# Wise-1570-v1_0.net
KiCad netlist of a schematic drawn in EAGLE
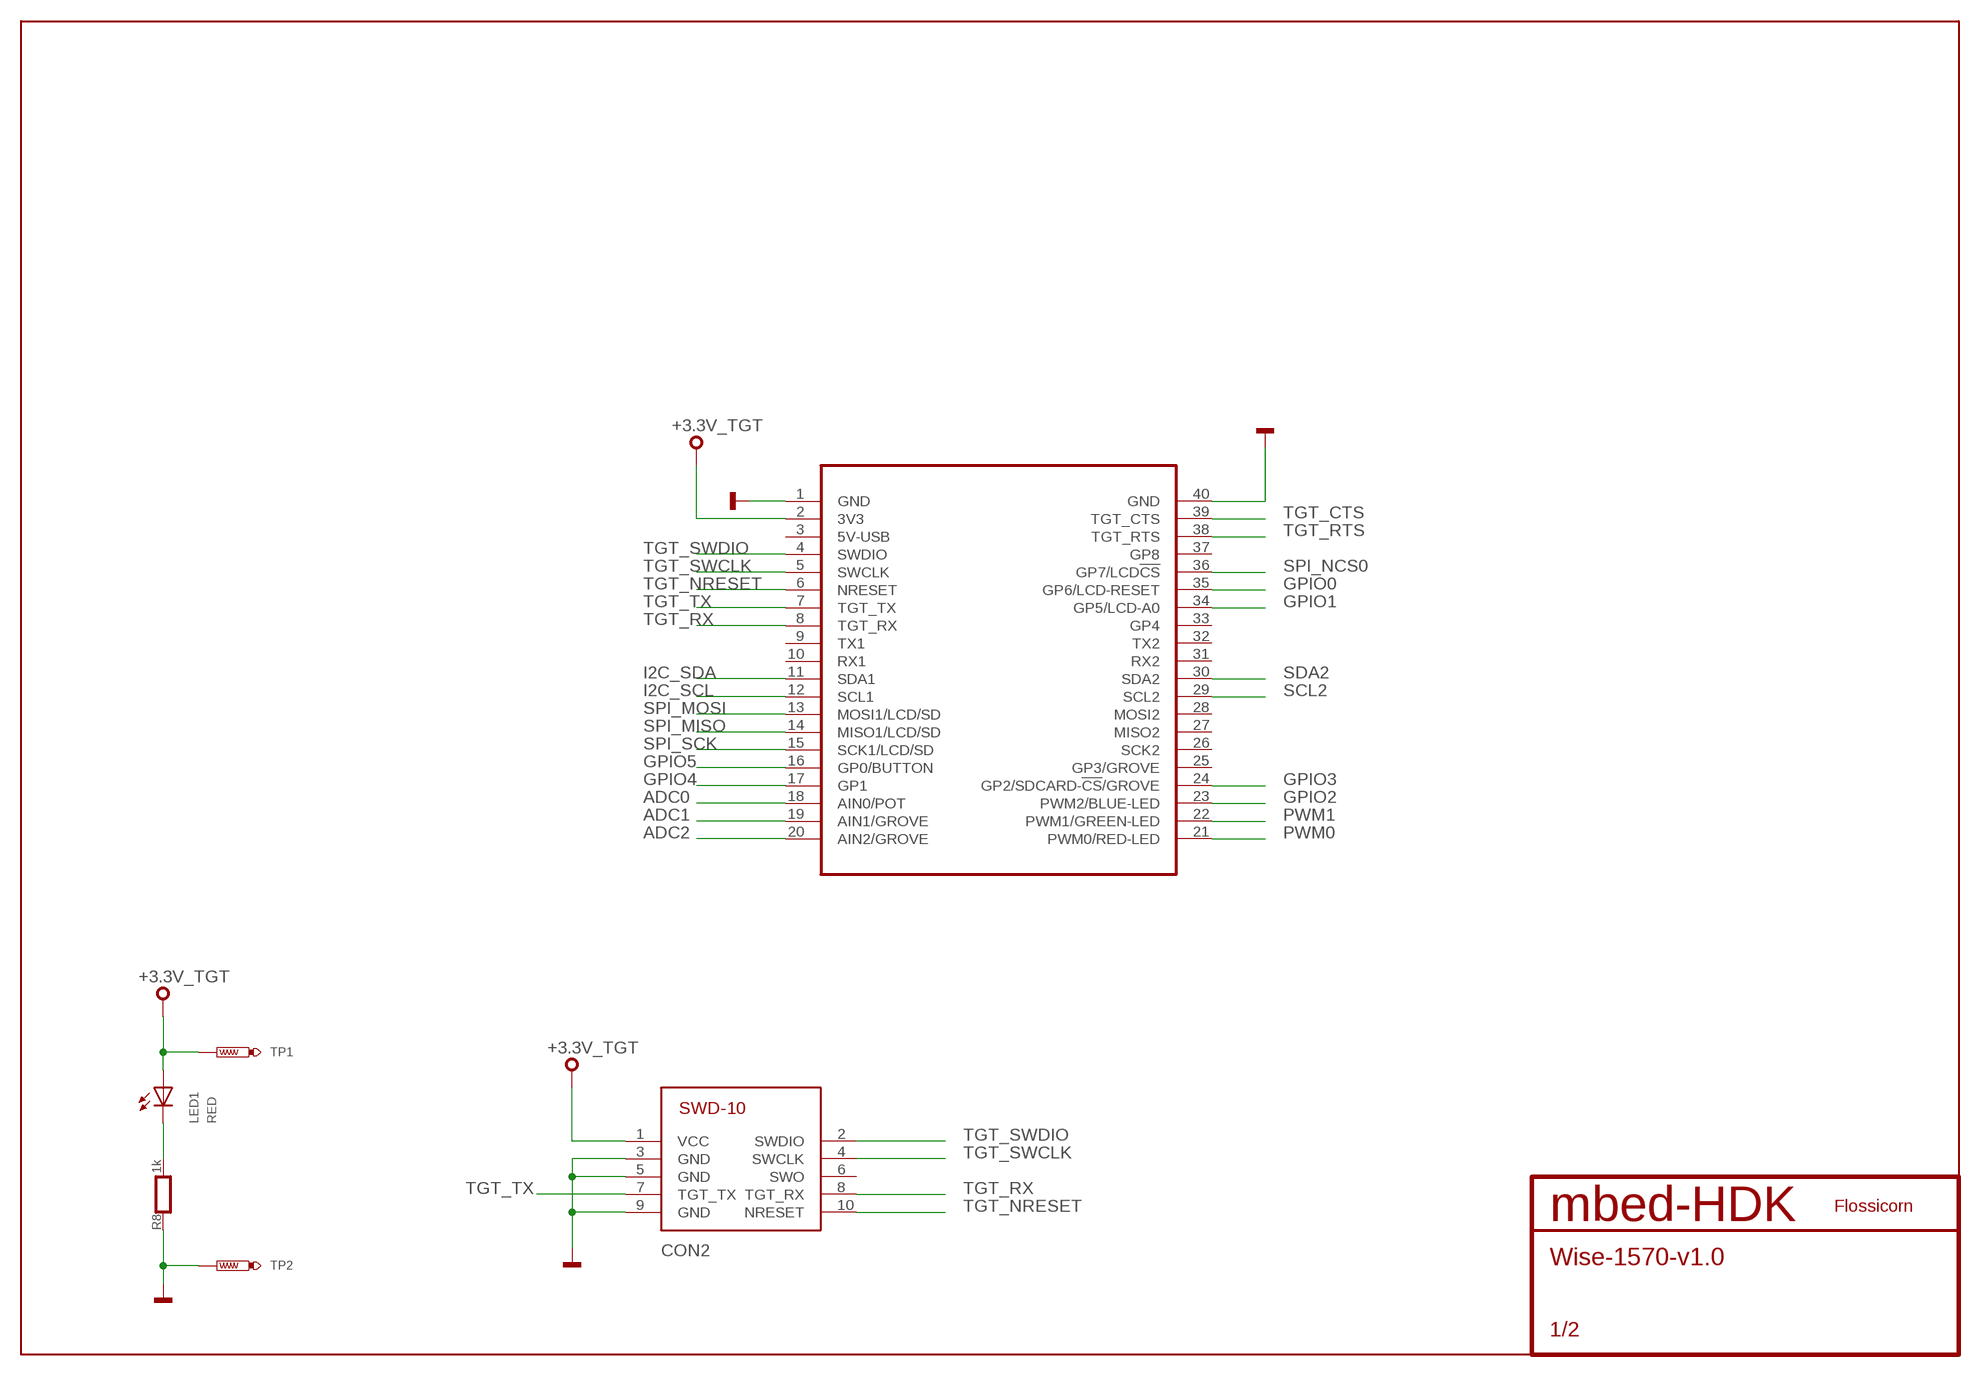
[diagram p0: schematic, sheet 1]
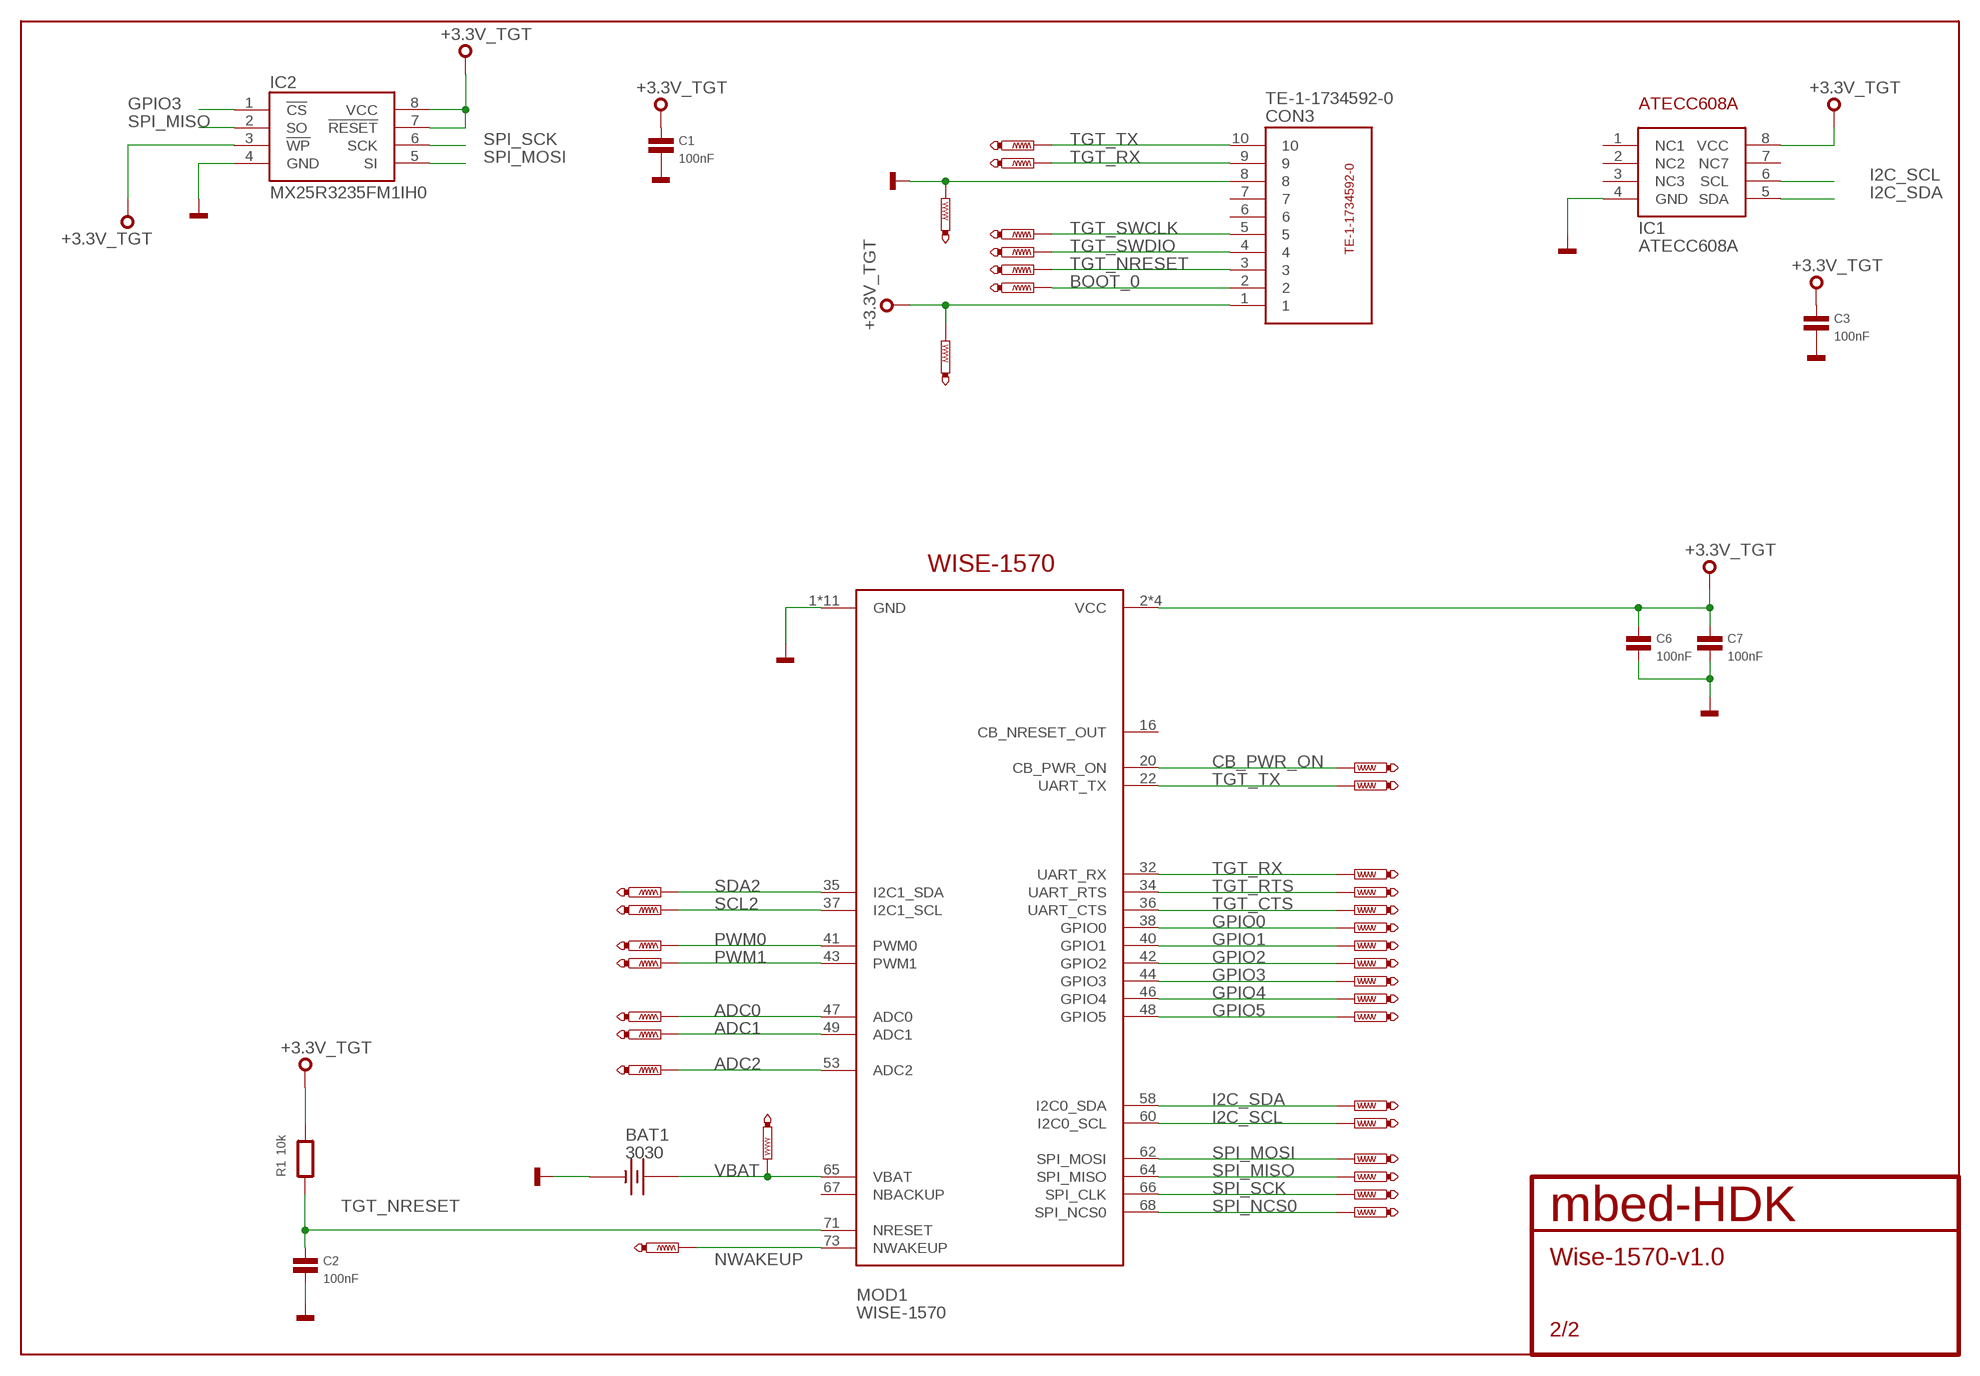
[diagram p1: schematic, sheet 2]

(export (version "E")
  (design (tool "Eeschema 10.0.6"))
  (components
    (comp (ref "CON2")
      (value "SWD-10/TC2050_SMD")
      (footprint "eagle-import:FTSH-105-02")
      (libsource (lib "eagle-import") (part "SWD-10/TC2050_SMD"))
    )
    (comp (ref "LED1")
      (value "RED")
      (footprint "eagle-import:CHIPLED_0603")
      (fields (field (name "MF") "Wurth Electronics Inc"))
      (libsource (lib "eagle-import") (part "SMD_LED0603"))
    )
    (comp (ref "MOD2")
      (value "MODULE_DAUGHTER")
      (footprint "eagle-import:MODULE_DAUGHTER")
      (libsource (lib "eagle-import") (part "MODULE_DAUGHTER"))
    )
    (comp (ref "R8")
      (value "1k")
      (footprint "eagle-import:0603")
      (libsource (lib "eagle-import") (part "RESISTOR0603"))
    )
    (comp (ref "SS1")
      (value "FLOSSICORN0.25")
      (footprint "eagle-import:FLOSSICORN-0.25")
      (libsource (lib "eagle-import") (part "FLOSSICORN0.25"))
    )
    (comp (ref "TP1")
      (value "TEST-POINT-50R-PTH")
      (footprint "eagle-import:TP50-PTH")
      (libsource (lib "eagle-import") (part "TEST-POINT-50R-PTH"))
    )
    (comp (ref "TP2")
      (value "TEST-POINT-50R-PTH")
      (footprint "eagle-import:TP50-PTH")
      (libsource (lib "eagle-import") (part "TEST-POINT-50R-PTH"))
    )
    (comp (ref "BAT1")
      (value "3030")
      (footprint "eagle-import:3030")
      (fields (field (name "MF") "Keystone"))
      (libsource (lib "eagle-import") (part "3030"))
    )
    (comp (ref "C1")
      (value "100nF")
      (footprint "eagle-import:0603")
      (libsource (lib "eagle-import") (part "CAPACITOR0603"))
    )
    (comp (ref "C2")
      (value "100nF")
      (footprint "eagle-import:0603")
      (libsource (lib "eagle-import") (part "CAPACITOR0603"))
    )
    (comp (ref "C3")
      (value "100nF")
      (footprint "eagle-import:0603")
      (libsource (lib "eagle-import") (part "CAPACITOR0603"))
    )
    (comp (ref "C6")
      (value "100nF")
      (footprint "eagle-import:0603")
      (libsource (lib "eagle-import") (part "CAPACITOR0603"))
    )
    (comp (ref "C7")
      (value "100nF")
      (footprint "eagle-import:0603")
      (libsource (lib "eagle-import") (part "CAPACITOR0603"))
    )
    (comp (ref "CON3")
      (value "TE-1-1734592-0")
      (footprint "eagle-import:TE-1-1734592-0")
      (libsource (lib "eagle-import") (part "TE-1-1734592-0"))
    )
    (comp (ref "IC1")
      (value "ATECC608A")
      (footprint "eagle-import:SO8")
      (libsource (lib "eagle-import") (part "ATECC608A"))
    )
    (comp (ref "IC2")
      (value "MX25R3235FM1IH0")
      (footprint "eagle-import:SO8")
      (fields (field (name "MF") "Macronix"))
      (libsource (lib "eagle-import") (part "MX25R3235FM1IH0"))
    )
    (comp (ref "MOD1")
      (value "WISE-1570")
      (footprint "eagle-import:MDT420E02001")
      (libsource (lib "eagle-import") (part "WISE-1570"))
    )
    (comp (ref "R1")
      (value "10k")
      (footprint "eagle-import:0603")
      (libsource (lib "eagle-import") (part "RESISTOR0603"))
    )
    (comp (ref "TP3")
      (value "PTR1TP08R")
      (footprint "eagle-import:TP08R")
      (libsource (lib "eagle-import") (part "PTR1TP08R"))
    )
    (comp (ref "TP4")
      (value "PTR1TP08R")
      (footprint "eagle-import:TP08R")
      (libsource (lib "eagle-import") (part "PTR1TP08R"))
    )
    (comp (ref "TP5")
      (value "PTR1TP08R")
      (footprint "eagle-import:TP08R")
      (libsource (lib "eagle-import") (part "PTR1TP08R"))
    )
    (comp (ref "TP6")
      (value "PTR1TP08R")
      (footprint "eagle-import:TP08R")
      (libsource (lib "eagle-import") (part "PTR1TP08R"))
    )
    (comp (ref "TP7")
      (value "PTR1TP08R")
      (footprint "eagle-import:TP08R")
      (libsource (lib "eagle-import") (part "PTR1TP08R"))
    )
    (comp (ref "TP8")
      (value "PTR1TP08R")
      (footprint "eagle-import:TP08R")
      (libsource (lib "eagle-import") (part "PTR1TP08R"))
    )
    (comp (ref "TP9")
      (value "PTR1TP07R")
      (footprint "eagle-import:TP07R")
      (libsource (lib "eagle-import") (part "PTR1TP07R"))
    )
    (comp (ref "TP10")
      (value "PTR1TP07R")
      (footprint "eagle-import:TP07R")
      (libsource (lib "eagle-import") (part "PTR1TP07R"))
    )
    (comp (ref "TP11")
      (value "PTR1TP07R")
      (footprint "eagle-import:TP07R")
      (libsource (lib "eagle-import") (part "PTR1TP07R"))
    )
    (comp (ref "TP12")
      (value "PTR1TP08R")
      (footprint "eagle-import:TP08R")
      (libsource (lib "eagle-import") (part "PTR1TP08R"))
    )
    (comp (ref "TP13")
      (value "PTR1TP08R")
      (footprint "eagle-import:TP08R")
      (libsource (lib "eagle-import") (part "PTR1TP08R"))
    )
    (comp (ref "TP14")
      (value "PTR1TP07R")
      (footprint "eagle-import:TP07R")
      (libsource (lib "eagle-import") (part "PTR1TP07R"))
    )
    (comp (ref "TP15")
      (value "PTR1TP07R")
      (footprint "eagle-import:TP07R")
      (libsource (lib "eagle-import") (part "PTR1TP07R"))
    )
    (comp (ref "TP16")
      (value "PTR1TP07R")
      (footprint "eagle-import:TP07R")
      (libsource (lib "eagle-import") (part "PTR1TP07R"))
    )
    (comp (ref "TP17")
      (value "PTR1TP07R")
      (footprint "eagle-import:TP07R")
      (libsource (lib "eagle-import") (part "PTR1TP07R"))
    )
    (comp (ref "TP18")
      (value "PTR1TP07R")
      (footprint "eagle-import:TP07R")
      (libsource (lib "eagle-import") (part "PTR1TP07R"))
    )
    (comp (ref "TP19")
      (value "PTR1TP07R")
      (footprint "eagle-import:TP07R")
      (libsource (lib "eagle-import") (part "PTR1TP07R"))
    )
    (comp (ref "TP20")
      (value "PTR1TP07R")
      (footprint "eagle-import:TP07R")
      (libsource (lib "eagle-import") (part "PTR1TP07R"))
    )
    (comp (ref "TP21")
      (value "PTR1TP07R")
      (footprint "eagle-import:TP07R")
      (libsource (lib "eagle-import") (part "PTR1TP07R"))
    )
    (comp (ref "TP22")
      (value "PTR1TP07R")
      (footprint "eagle-import:TP07R")
      (libsource (lib "eagle-import") (part "PTR1TP07R"))
    )
    (comp (ref "TP23")
      (value "PTR1TP07R")
      (footprint "eagle-import:TP07R")
      (libsource (lib "eagle-import") (part "PTR1TP07R"))
    )
    (comp (ref "TP24")
      (value "PTR1TP07R")
      (footprint "eagle-import:TP07R")
      (libsource (lib "eagle-import") (part "PTR1TP07R"))
    )
    (comp (ref "TP25")
      (value "PTR1TP07R")
      (footprint "eagle-import:TP07R")
      (libsource (lib "eagle-import") (part "PTR1TP07R"))
    )
    (comp (ref "TP26")
      (value "PTR1TP07R")
      (footprint "eagle-import:TP07R")
      (libsource (lib "eagle-import") (part "PTR1TP07R"))
    )
    (comp (ref "TP27")
      (value "PTR1TP07R")
      (footprint "eagle-import:TP07R")
      (libsource (lib "eagle-import") (part "PTR1TP07R"))
    )
    (comp (ref "TP28")
      (value "PTR1TP07R")
      (footprint "eagle-import:TP07R")
      (libsource (lib "eagle-import") (part "PTR1TP07R"))
    )
    (comp (ref "TP29")
      (value "PTR1TP07R")
      (footprint "eagle-import:TP07R")
      (libsource (lib "eagle-import") (part "PTR1TP07R"))
    )
    (comp (ref "TP30")
      (value "PTR1TP07R")
      (footprint "eagle-import:TP07R")
      (libsource (lib "eagle-import") (part "PTR1TP07R"))
    )
    (comp (ref "TP31")
      (value "PTR1TP07R")
      (footprint "eagle-import:TP07R")
      (libsource (lib "eagle-import") (part "PTR1TP07R"))
    )
    (comp (ref "TP32")
      (value "PTR1TP07R")
      (footprint "eagle-import:TP07R")
      (libsource (lib "eagle-import") (part "PTR1TP07R"))
    )
    (comp (ref "TP33")
      (value "PTR1TP07R")
      (footprint "eagle-import:TP07R")
      (libsource (lib "eagle-import") (part "PTR1TP07R"))
    )
    (comp (ref "TP34")
      (value "PTR1TP07R")
      (footprint "eagle-import:TP07R")
      (libsource (lib "eagle-import") (part "PTR1TP07R"))
    )
    (comp (ref "TP35")
      (value "PTR1TP07R")
      (footprint "eagle-import:TP07R")
      (libsource (lib "eagle-import") (part "PTR1TP07R"))
    )
    (comp (ref "TP36")
      (value "PTR1TP07R")
      (footprint "eagle-import:TP07R")
      (libsource (lib "eagle-import") (part "PTR1TP07R"))
    )
  )
  (nets
    (net (code "1") (name "+3.3V_TGT") (class "Default")
      (node (ref "C1") (pin "1") (pinfunction "P$1_1") (pintype "passive"))
      (node (ref "C3") (pin "1") (pinfunction "P$1_1") (pintype "passive"))
      (node (ref "C6") (pin "1") (pinfunction "P$1_1") (pintype "passive"))
      (node (ref "C7") (pin "1") (pinfunction "P$1_1") (pintype "passive"))
      (node (ref "CON2") (pin "1") (pinfunction "VCC_1") (pintype "bidirectional"))
      (node (ref "CON3") (pin "1") (pinfunction "1_1") (pintype "bidirectional"))
      (node (ref "IC1") (pin "8") (pinfunction "VCC_8") (pintype "bidirectional"))
      (node (ref "IC2") (pin "3") (pinfunction "~{WP}_3") (pintype "bidirectional"))
      (node (ref "IC2") (pin "7") (pinfunction "~{RESET}_7") (pintype "bidirectional"))
      (node (ref "IC2") (pin "8") (pinfunction "VCC_8") (pintype "bidirectional"))
      (node (ref "LED1") (pin "A") (pinfunction "A_A") (pintype "passive"))
      (node (ref "MOD1") (pin "2") (pinfunction "VCC_2") (pintype "bidirectional"))
      (node (ref "MOD1") (pin "4") (pinfunction "VCC_4") (pintype "bidirectional"))
      (node (ref "MOD1") (pin "72") (pinfunction "VCC_72") (pintype "bidirectional"))
      (node (ref "MOD1") (pin "74") (pinfunction "VCC_74") (pintype "bidirectional"))
      (node (ref "MOD2") (pin "2") (pinfunction "3V3_2") (pintype "bidirectional"))
      (node (ref "R1") (pin "2") (pinfunction "P$2_2") (pintype "passive"))
      (node (ref "TP1") (pin "TP") (pinfunction "TP_TP") (pintype "input"))
      (node (ref "TP12") (pin "TP") (pinfunction "TP_TP") (pintype "input"))
    )
    (net (code "2") (name "ADC0") (class "Default")
      (node (ref "MOD1") (pin "47") (pinfunction "ADC0_47") (pintype "bidirectional"))
      (node (ref "MOD2") (pin "18") (pinfunction "AIN0/POT_18") (pintype "bidirectional"))
      (node (ref "TP29") (pin "TP") (pinfunction "TP_TP") (pintype "input"))
    )
    (net (code "3") (name "ADC1") (class "Default")
      (node (ref "MOD1") (pin "49") (pinfunction "ADC1_49") (pintype "bidirectional"))
      (node (ref "MOD2") (pin "19") (pinfunction "AIN1/GROVE_19") (pintype "bidirectional"))
      (node (ref "TP30") (pin "TP") (pinfunction "TP_TP") (pintype "input"))
    )
    (net (code "4") (name "ADC2") (class "Default")
      (node (ref "MOD1") (pin "53") (pinfunction "ADC2_53") (pintype "bidirectional"))
      (node (ref "MOD2") (pin "20") (pinfunction "AIN2/GROVE_20") (pintype "bidirectional"))
      (node (ref "TP31") (pin "TP") (pinfunction "TP_TP") (pintype "input"))
    )
    (net (code "5") (name "BOOT_0") (class "Default")
      (node (ref "CON3") (pin "2") (pinfunction "2_2") (pintype "bidirectional"))
      (node (ref "TP8") (pin "TP") (pinfunction "TP_TP") (pintype "input"))
    )
    (net (code "6") (name "CB_PWR_ON") (class "Default")
      (node (ref "MOD1") (pin "20") (pinfunction "CB_PWR_ON_20") (pintype "bidirectional"))
      (node (ref "TP14") (pin "TP") (pinfunction "TP_TP") (pintype "input"))
    )
    (net (code "7") (name "GND") (class "Default")
      (node (ref "BAT1") (pin "-") (pinfunction "-_-") (pintype "bidirectional"))
      (node (ref "C1") (pin "2") (pinfunction "P$2_2") (pintype "passive"))
      (node (ref "C2") (pin "2") (pinfunction "P$2_2") (pintype "passive"))
      (node (ref "C3") (pin "2") (pinfunction "P$2_2") (pintype "passive"))
      (node (ref "C6") (pin "2") (pinfunction "P$2_2") (pintype "passive"))
      (node (ref "C7") (pin "2") (pinfunction "P$2_2") (pintype "passive"))
      (node (ref "CON2") (pin "3") (pinfunction "GND_3") (pintype "bidirectional"))
      (node (ref "CON2") (pin "5") (pinfunction "GND_5") (pintype "bidirectional"))
      (node (ref "CON2") (pin "9") (pinfunction "GND_9") (pintype "bidirectional"))
      (node (ref "CON3") (pin "8") (pinfunction "8_8") (pintype "bidirectional"))
      (node (ref "IC1") (pin "4") (pinfunction "GND_4") (pintype "bidirectional"))
      (node (ref "IC2") (pin "4") (pinfunction "GND_4") (pintype "bidirectional"))
      (node (ref "MOD1") (pin "1") (pinfunction "GND_1") (pintype "bidirectional"))
      (node (ref "MOD1") (pin "18") (pinfunction "GND_18") (pintype "bidirectional"))
      (node (ref "MOD1") (pin "33") (pinfunction "GND_33") (pintype "bidirectional"))
      (node (ref "MOD1") (pin "39") (pinfunction "GND_39") (pintype "bidirectional"))
      (node (ref "MOD1") (pin "45") (pinfunction "GND_45") (pintype "bidirectional"))
      (node (ref "MOD1") (pin "51") (pinfunction "GND_51") (pintype "bidirectional"))
      (node (ref "MOD1") (pin "57") (pinfunction "GND_57") (pintype "bidirectional"))
      (node (ref "MOD1") (pin "63") (pinfunction "GND_63") (pintype "bidirectional"))
      (node (ref "MOD1") (pin "69") (pinfunction "GND_69") (pintype "bidirectional"))
      (node (ref "MOD1") (pin "7") (pinfunction "GND_7") (pintype "bidirectional"))
      (node (ref "MOD1") (pin "75") (pinfunction "GND_75") (pintype "bidirectional"))
      (node (ref "MOD2") (pin "1") (pinfunction "GND_1") (pintype "bidirectional"))
      (node (ref "MOD2") (pin "40") (pinfunction "GND_40") (pintype "bidirectional"))
      (node (ref "R8") (pin "1") (pinfunction "P$1_1") (pintype "passive"))
      (node (ref "TP13") (pin "TP") (pinfunction "TP_TP") (pintype "input"))
      (node (ref "TP2") (pin "TP") (pinfunction "TP_TP") (pintype "input"))
    )
    (net (code "8") (name "GPIO0") (class "Default")
      (node (ref "MOD1") (pin "38") (pinfunction "GPIO0_38") (pintype "bidirectional"))
      (node (ref "MOD2") (pin "35") (pinfunction "GP6/LCD-RESET_35") (pintype "bidirectional"))
      (node (ref "TP27") (pin "TP") (pinfunction "TP_TP") (pintype "input"))
    )
    (net (code "9") (name "GPIO1") (class "Default")
      (node (ref "MOD1") (pin "40") (pinfunction "GPIO1_40") (pintype "bidirectional"))
      (node (ref "MOD2") (pin "34") (pinfunction "GP5/LCD-A0_34") (pintype "bidirectional"))
      (node (ref "TP26") (pin "TP") (pinfunction "TP_TP") (pintype "input"))
    )
    (net (code "10") (name "GPIO2") (class "Default")
      (node (ref "MOD1") (pin "42") (pinfunction "GPIO2_42") (pintype "bidirectional"))
      (node (ref "MOD2") (pin "23") (pinfunction "PWM2/BLUE-LED_23") (pintype "bidirectional"))
      (node (ref "TP32") (pin "TP") (pinfunction "TP_TP") (pintype "input"))
    )
    (net (code "11") (name "GPIO3") (class "Default")
      (node (ref "IC2") (pin "1") (pinfunction "~{CS}_1") (pintype "bidirectional"))
      (node (ref "MOD1") (pin "44") (pinfunction "GPIO3_44") (pintype "bidirectional"))
      (node (ref "MOD2") (pin "24") (pinfunction "GP2/SDCARD-~{CS}/GROVE_24") (pintype "bidirectional"))
      (node (ref "TP25") (pin "TP") (pinfunction "TP_TP") (pintype "input"))
    )
    (net (code "12") (name "GPIO4") (class "Default")
      (node (ref "MOD1") (pin "46") (pinfunction "GPIO4_46") (pintype "bidirectional"))
      (node (ref "MOD2") (pin "17") (pinfunction "GP1_17") (pintype "bidirectional"))
      (node (ref "TP24") (pin "TP") (pinfunction "TP_TP") (pintype "input"))
    )
    (net (code "13") (name "GPIO5") (class "Default")
      (node (ref "MOD1") (pin "48") (pinfunction "GPIO5_48") (pintype "bidirectional"))
      (node (ref "MOD2") (pin "16") (pinfunction "GP0/BUTTON_16") (pintype "bidirectional"))
      (node (ref "TP23") (pin "TP") (pinfunction "TP_TP") (pintype "input"))
    )
    (net (code "14") (name "I2C_SCL") (class "Default")
      (node (ref "IC1") (pin "6") (pinfunction "SCL_6") (pintype "bidirectional"))
      (node (ref "MOD1") (pin "60") (pinfunction "I2C0_SCL_60") (pintype "bidirectional"))
      (node (ref "MOD2") (pin "12") (pinfunction "SCL1_12") (pintype "bidirectional"))
      (node (ref "TP20") (pin "TP") (pinfunction "TP_TP") (pintype "input"))
    )
    (net (code "15") (name "I2C_SDA") (class "Default")
      (node (ref "IC1") (pin "5") (pinfunction "SDA_5") (pintype "bidirectional"))
      (node (ref "MOD1") (pin "58") (pinfunction "I2C0_SDA_58") (pintype "bidirectional"))
      (node (ref "MOD2") (pin "11") (pinfunction "SDA1_11") (pintype "bidirectional"))
      (node (ref "TP21") (pin "TP") (pinfunction "TP_TP") (pintype "input"))
    )
    (net (code "16") (name "NWAKEUP") (class "Default")
      (node (ref "MOD1") (pin "73") (pinfunction "NWAKEUP_73") (pintype "bidirectional"))
      (node (ref "TP34") (pin "TP") (pinfunction "TP_TP") (pintype "input"))
    )
    (net (code "17") (name "Net-(R8-P$2)") (class "Default")
      (node (ref "LED1") (pin "C") (pinfunction "C_C") (pintype "passive"))
      (node (ref "R8") (pin "2") (pinfunction "P$2_2") (pintype "passive"))
    )
    (net (code "18") (name "PWM0") (class "Default")
      (node (ref "MOD1") (pin "41") (pinfunction "PWM0_41") (pintype "bidirectional"))
      (node (ref "MOD2") (pin "21") (pinfunction "PWM0/RED-LED_21") (pintype "bidirectional"))
      (node (ref "TP16") (pin "TP") (pinfunction "TP_TP") (pintype "input"))
    )
    (net (code "19") (name "PWM1") (class "Default")
      (node (ref "MOD1") (pin "43") (pinfunction "PWM1_43") (pintype "bidirectional"))
      (node (ref "MOD2") (pin "22") (pinfunction "PWM1/GREEN-LED_22") (pintype "bidirectional"))
      (node (ref "TP17") (pin "TP") (pinfunction "TP_TP") (pintype "input"))
    )
    (net (code "20") (name "SCL2") (class "Default")
      (node (ref "MOD1") (pin "37") (pinfunction "I2C1_SCL_37") (pintype "bidirectional"))
      (node (ref "MOD2") (pin "29") (pinfunction "SCL2_29") (pintype "bidirectional"))
      (node (ref "TP36") (pin "TP") (pinfunction "TP_TP") (pintype "input"))
    )
    (net (code "21") (name "SDA2") (class "Default")
      (node (ref "MOD1") (pin "35") (pinfunction "I2C1_SDA_35") (pintype "bidirectional"))
      (node (ref "MOD2") (pin "30") (pinfunction "SDA2_30") (pintype "bidirectional"))
      (node (ref "TP35") (pin "TP") (pinfunction "TP_TP") (pintype "input"))
    )
    (net (code "22") (name "SPI_MISO") (class "Default")
      (node (ref "IC2") (pin "2") (pinfunction "SO_2") (pintype "bidirectional"))
      (node (ref "MOD1") (pin "64") (pinfunction "SPI_MISO_64") (pintype "bidirectional"))
      (node (ref "MOD2") (pin "14") (pinfunction "MISO1/LCD/SD_14") (pintype "bidirectional"))
      (node (ref "TP11") (pin "TP") (pinfunction "TP_TP") (pintype "input"))
    )
    (net (code "23") (name "SPI_MOSI") (class "Default")
      (node (ref "IC2") (pin "5") (pinfunction "SI_5") (pintype "bidirectional"))
      (node (ref "MOD1") (pin "62") (pinfunction "SPI_MOSI_62") (pintype "bidirectional"))
      (node (ref "MOD2") (pin "13") (pinfunction "MOSI1/LCD/SD_13") (pintype "bidirectional"))
      (node (ref "TP22") (pin "TP") (pinfunction "TP_TP") (pintype "input"))
    )
    (net (code "24") (name "SPI_NCS0") (class "Default")
      (node (ref "MOD1") (pin "68") (pinfunction "SPI_NCS0_68") (pintype "bidirectional"))
      (node (ref "MOD2") (pin "36") (pinfunction "GP7/LCD~{CS}_36") (pintype "bidirectional"))
      (node (ref "TP9") (pin "TP") (pinfunction "TP_TP") (pintype "input"))
    )
    (net (code "25") (name "SPI_SCK") (class "Default")
      (node (ref "IC2") (pin "6") (pinfunction "SCK_6") (pintype "bidirectional"))
      (node (ref "MOD1") (pin "66") (pinfunction "SPI_CLK_66") (pintype "bidirectional"))
      (node (ref "MOD2") (pin "15") (pinfunction "SCK1/LCD/SD_15") (pintype "bidirectional"))
      (node (ref "TP10") (pin "TP") (pinfunction "TP_TP") (pintype "input"))
    )
    (net (code "26") (name "TGT_CTS") (class "Default")
      (node (ref "MOD1") (pin "36") (pinfunction "UART_CTS_36") (pintype "bidirectional"))
      (node (ref "MOD2") (pin "39") (pinfunction "TGT_CTS_39") (pintype "bidirectional"))
      (node (ref "TP19") (pin "TP") (pinfunction "TP_TP") (pintype "input"))
    )
    (net (code "27") (name "TGT_NRESET") (class "Default")
      (node (ref "C2") (pin "1") (pinfunction "P$1_1") (pintype "passive"))
      (node (ref "CON2") (pin "10") (pinfunction "NRESET_10") (pintype "bidirectional"))
      (node (ref "CON3") (pin "3") (pinfunction "3_3") (pintype "bidirectional"))
      (node (ref "MOD1") (pin "71") (pinfunction "NRESET_71") (pintype "bidirectional"))
      (node (ref "MOD2") (pin "6") (pinfunction "NRESET_6") (pintype "bidirectional"))
      (node (ref "R1") (pin "1") (pinfunction "P$1_1") (pintype "passive"))
      (node (ref "TP5") (pin "TP") (pinfunction "TP_TP") (pintype "input"))
    )
    (net (code "28") (name "TGT_RTS") (class "Default")
      (node (ref "MOD1") (pin "34") (pinfunction "UART_RTS_34") (pintype "bidirectional"))
      (node (ref "MOD2") (pin "38") (pinfunction "TGT_RTS_38") (pintype "bidirectional"))
      (node (ref "TP18") (pin "TP") (pinfunction "TP_TP") (pintype "input"))
    )
    (net (code "29") (name "TGT_RX") (class "Default")
      (node (ref "CON2") (pin "8") (pinfunction "TGT_RX_8") (pintype "bidirectional"))
      (node (ref "CON3") (pin "9") (pinfunction "9_9") (pintype "bidirectional"))
      (node (ref "MOD1") (pin "32") (pinfunction "UART_RX_32") (pintype "bidirectional"))
      (node (ref "MOD2") (pin "8") (pinfunction "TGT_RX_8") (pintype "bidirectional"))
      (node (ref "TP28") (pin "TP") (pinfunction "TP_TP") (pintype "input"))
      (node (ref "TP6") (pin "TP") (pinfunction "TP_TP") (pintype "input"))
    )
    (net (code "30") (name "TGT_SWCLK") (class "Default")
      (node (ref "CON2") (pin "4") (pinfunction "SWCLK_4") (pintype "bidirectional"))
      (node (ref "CON3") (pin "5") (pinfunction "5_5") (pintype "bidirectional"))
      (node (ref "MOD2") (pin "5") (pinfunction "SWCLK_5") (pintype "bidirectional"))
      (node (ref "TP3") (pin "TP") (pinfunction "TP_TP") (pintype "input"))
    )
    (net (code "31") (name "TGT_SWDIO") (class "Default")
      (node (ref "CON2") (pin "2") (pinfunction "SWDIO_2") (pintype "bidirectional"))
      (node (ref "CON3") (pin "4") (pinfunction "4_4") (pintype "bidirectional"))
      (node (ref "MOD2") (pin "4") (pinfunction "SWDIO_4") (pintype "bidirectional"))
      (node (ref "TP4") (pin "TP") (pinfunction "TP_TP") (pintype "input"))
    )
    (net (code "32") (name "TGT_TX") (class "Default")
      (node (ref "CON2") (pin "7") (pinfunction "TGT_TX_7") (pintype "bidirectional"))
      (node (ref "CON3") (pin "10") (pinfunction "10_10") (pintype "bidirectional"))
      (node (ref "MOD1") (pin "22") (pinfunction "UART_TX_22") (pintype "bidirectional"))
      (node (ref "MOD2") (pin "7") (pinfunction "TGT_TX_7") (pintype "bidirectional"))
      (node (ref "TP15") (pin "TP") (pinfunction "TP_TP") (pintype "input"))
      (node (ref "TP7") (pin "TP") (pinfunction "TP_TP") (pintype "input"))
    )
    (net (code "33") (name "VBAT") (class "Default")
      (node (ref "BAT1") (pin "+1") (pinfunction "+_+1") (pintype "bidirectional"))
      (node (ref "BAT1") (pin "+2") (pinfunction "+_+2") (pintype "bidirectional"))
      (node (ref "MOD1") (pin "65") (pinfunction "VBAT_65") (pintype "bidirectional"))
      (node (ref "TP33") (pin "TP") (pinfunction "TP_TP") (pintype "input"))
    )
    (net (code "34") (name "unconnected-(CON2-SWO-Pad6)") (class "Default")
      (node (ref "CON2") (pin "6") (pinfunction "SWO_6") (pintype "bidirectional"))
    )
    (net (code "35") (name "unconnected-(CON3-Pad6)") (class "Default")
      (node (ref "CON3") (pin "6") (pinfunction "6_6") (pintype "bidirectional"))
    )
    (net (code "36") (name "unconnected-(CON3-Pad7)") (class "Default")
      (node (ref "CON3") (pin "7") (pinfunction "7_7") (pintype "bidirectional"))
    )
    (net (code "37") (name "unconnected-(IC1-NC1-Pad1)") (class "Default")
      (node (ref "IC1") (pin "1") (pinfunction "NC1_1") (pintype "bidirectional"))
    )
    (net (code "38") (name "unconnected-(IC1-NC2-Pad2)") (class "Default")
      (node (ref "IC1") (pin "2") (pinfunction "NC2_2") (pintype "bidirectional"))
    )
    (net (code "39") (name "unconnected-(IC1-NC3-Pad3)") (class "Default")
      (node (ref "IC1") (pin "3") (pinfunction "NC3_3") (pintype "bidirectional"))
    )
    (net (code "40") (name "unconnected-(IC1-NC7-Pad7)") (class "Default")
      (node (ref "IC1") (pin "7") (pinfunction "NC7_7") (pintype "bidirectional"))
    )
    (net (code "41") (name "unconnected-(MOD1-CB_NRESET_OUT-Pad16)") (class "Default")
      (node (ref "MOD1") (pin "16") (pinfunction "CB_NRESET_OUT_16") (pintype "bidirectional"))
    )
    (net (code "42") (name "unconnected-(MOD1-NBACKUP-Pad67)") (class "Default")
      (node (ref "MOD1") (pin "67") (pinfunction "NBACKUP_67") (pintype "bidirectional"))
    )
    (net (code "43") (name "unconnected-(MOD2-5V-USB-Pad3)") (class "Default")
      (node (ref "MOD2") (pin "3") (pinfunction "5V-USB_3") (pintype "bidirectional"))
    )
    (net (code "44") (name "unconnected-(MOD2-GP3{slash}GROVE-Pad25)") (class "Default")
      (node (ref "MOD2") (pin "25") (pinfunction "GP3/GROVE_25") (pintype "bidirectional"))
    )
    (net (code "45") (name "unconnected-(MOD2-GP4-Pad33)") (class "Default")
      (node (ref "MOD2") (pin "33") (pinfunction "GP4_33") (pintype "bidirectional"))
    )
    (net (code "46") (name "unconnected-(MOD2-GP8-Pad37)") (class "Default")
      (node (ref "MOD2") (pin "37") (pinfunction "GP8_37") (pintype "bidirectional"))
    )
    (net (code "47") (name "unconnected-(MOD2-MISO2-Pad27)") (class "Default")
      (node (ref "MOD2") (pin "27") (pinfunction "MISO2_27") (pintype "bidirectional"))
    )
    (net (code "48") (name "unconnected-(MOD2-MOSI2-Pad28)") (class "Default")
      (node (ref "MOD2") (pin "28") (pinfunction "MOSI2_28") (pintype "bidirectional"))
    )
    (net (code "49") (name "unconnected-(MOD2-RX1-Pad10)") (class "Default")
      (node (ref "MOD2") (pin "10") (pinfunction "RX1_10") (pintype "bidirectional"))
    )
    (net (code "50") (name "unconnected-(MOD2-RX2-Pad31)") (class "Default")
      (node (ref "MOD2") (pin "31") (pinfunction "RX2_31") (pintype "bidirectional"))
    )
    (net (code "51") (name "unconnected-(MOD2-SCK2-Pad26)") (class "Default")
      (node (ref "MOD2") (pin "26") (pinfunction "SCK2_26") (pintype "bidirectional"))
    )
    (net (code "52") (name "unconnected-(MOD2-TX1-Pad9)") (class "Default")
      (node (ref "MOD2") (pin "9") (pinfunction "TX1_9") (pintype "bidirectional"))
    )
    (net (code "53") (name "unconnected-(MOD2-TX2-Pad32)") (class "Default")
      (node (ref "MOD2") (pin "32") (pinfunction "TX2_32") (pintype "bidirectional"))
    )
  )
)
